# secs_q84_v2.net
KiCad netlist of a schematic drawn in EAGLE
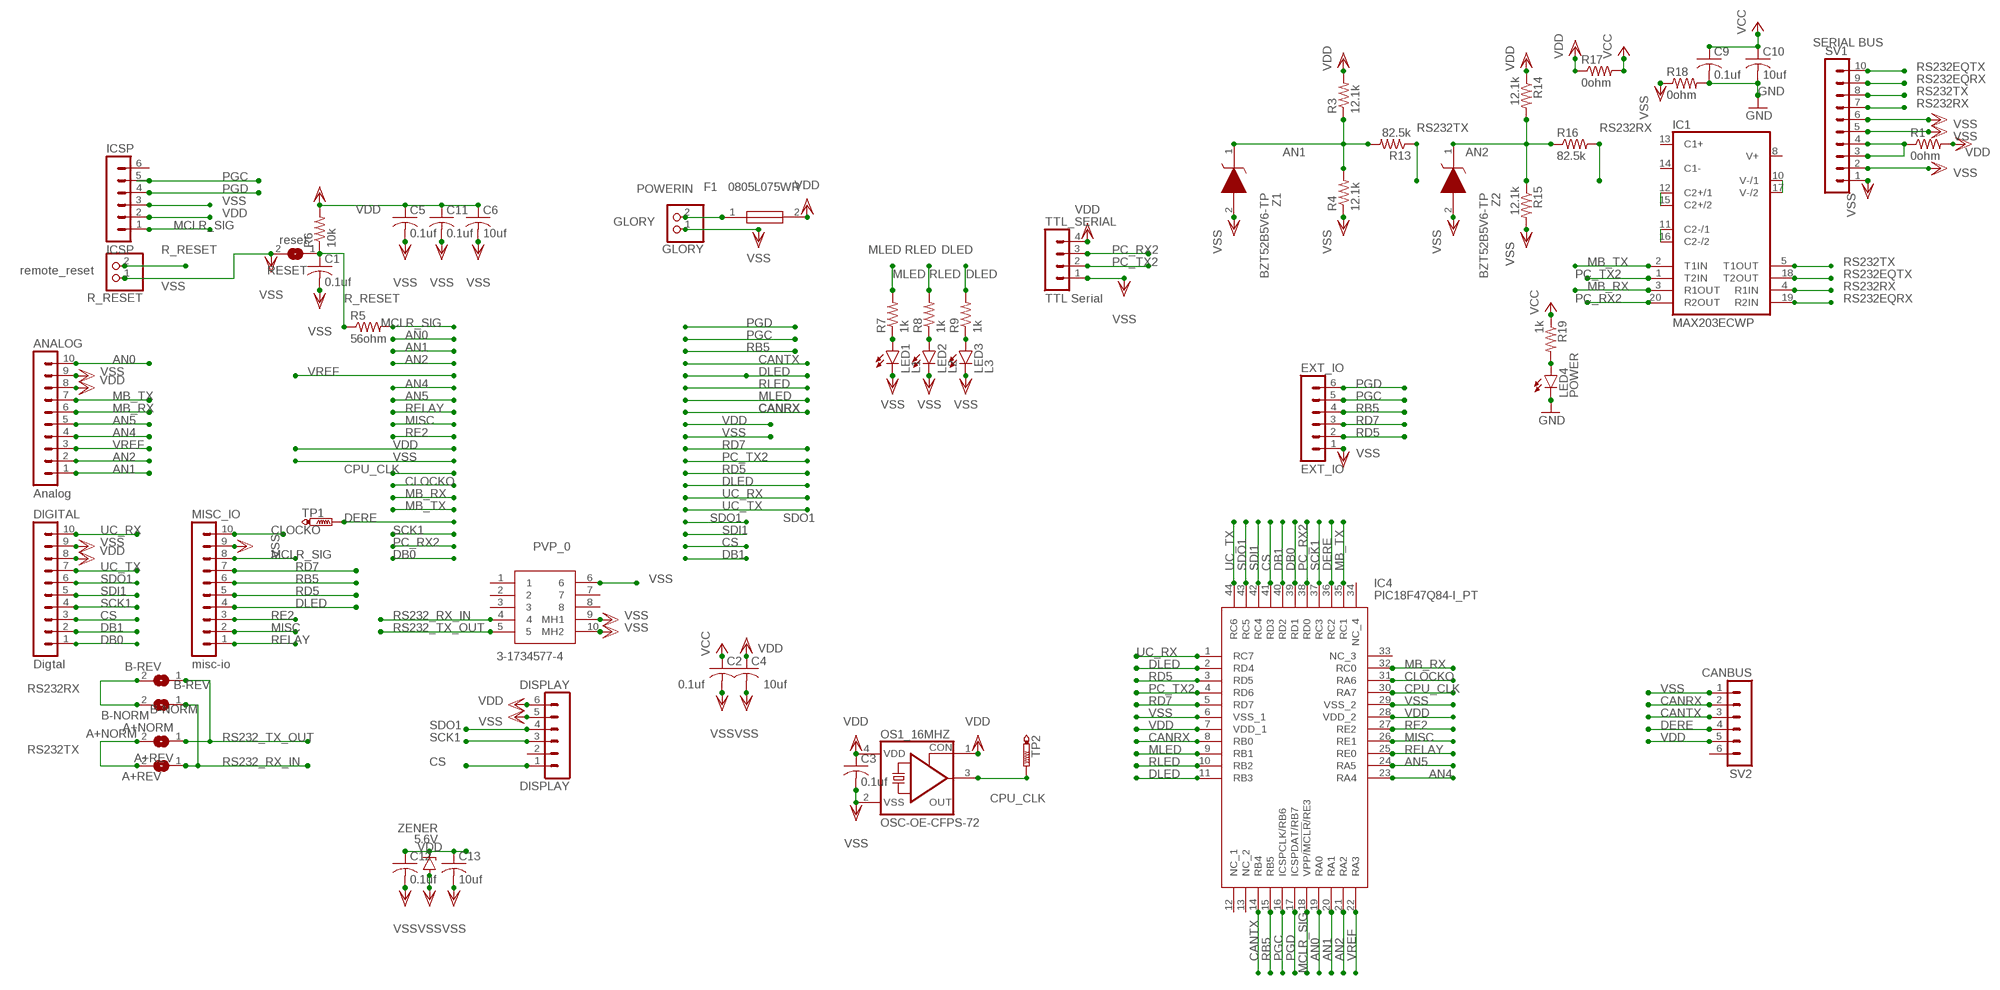
[diagram p0: schematic, sheet 1]

(export (version "E")
  (design (tool "Eeschema 10.0.6"))
  (components
    (comp (ref "A+NORM")
      (value "A+NORM")
      (footprint "eagle-import:SJ")
      (libsource (lib "eagle-import") (part "SJ"))
    )
    (comp (ref "A+REV")
      (value "A+REV")
      (footprint "eagle-import:SJ")
      (libsource (lib "eagle-import") (part "SJ"))
    )
    (comp (ref "ANALOG")
      (value "Analog")
      (footprint "eagle-import:MA10-1")
      (libsource (lib "eagle-import") (part "MA10-1"))
    )
    (comp (ref "B-NORM")
      (value "B-NORM")
      (footprint "eagle-import:SJ")
      (libsource (lib "eagle-import") (part "SJ"))
    )
    (comp (ref "B-REV")
      (value "B-REV")
      (footprint "eagle-import:SJ")
      (libsource (lib "eagle-import") (part "SJ"))
    )
    (comp (ref "C1")
      (value "0.1uf")
      (footprint "eagle-import:C0805")
      (libsource (lib "eagle-import") (part "C-USC0805"))
    )
    (comp (ref "C2")
      (value "0.1uf")
      (footprint "eagle-import:C0805")
      (libsource (lib "eagle-import") (part "C-USC0805"))
    )
    (comp (ref "C3")
      (value "0.1uf")
      (footprint "eagle-import:C0805")
      (libsource (lib "eagle-import") (part "C-USC0805"))
    )
    (comp (ref "C4")
      (value "10uf")
      (footprint "eagle-import:C0805")
      (libsource (lib "eagle-import") (part "C-USC0805"))
    )
    (comp (ref "C5")
      (value "0.1uf")
      (footprint "eagle-import:C0805")
      (libsource (lib "eagle-import") (part "C-USC0805"))
    )
    (comp (ref "C6")
      (value "10uf")
      (footprint "eagle-import:C0805")
      (libsource (lib "eagle-import") (part "C-USC0805"))
    )
    (comp (ref "C9")
      (value "0.1uf")
      (footprint "eagle-import:C0805")
      (libsource (lib "eagle-import") (part "C-USC0805"))
    )
    (comp (ref "C10")
      (value "10uf")
      (footprint "eagle-import:C0805")
      (libsource (lib "eagle-import") (part "C-USC0805"))
    )
    (comp (ref "C11")
      (value "0.1uf")
      (footprint "eagle-import:C0805")
      (libsource (lib "eagle-import") (part "C-USC0805"))
    )
    (comp (ref "C12")
      (value "0.1uf")
      (footprint "eagle-import:C0805")
      (libsource (lib "eagle-import") (part "C-USC0805"))
    )
    (comp (ref "C13")
      (value "10uf")
      (footprint "eagle-import:C0805")
      (libsource (lib "eagle-import") (part "C-USC0805"))
    )
    (comp (ref "DIGITAL")
      (value "Digtal")
      (footprint "eagle-import:MA10-1")
      (libsource (lib "eagle-import") (part "MA10-1"))
    )
    (comp (ref "DISPLAY")
      (value "DISPLAY")
      (footprint "eagle-import:MA06-1")
      (libsource (lib "eagle-import") (part "MA06-1"))
    )
    (comp (ref "EXT_IO")
      (value "EXT_IO")
      (footprint "eagle-import:MA06-1")
      (libsource (lib "eagle-import") (part "MA06-1"))
    )
    (comp (ref "F1")
      (value "0805L075WR")
      (footprint "eagle-import:FUSC2114X125N")
      (fields (field (name "MOUSER_PART_NUMBER") "576-0805L075WR"))
      (libsource (lib "eagle-import") (part "0805L075WR"))
    )
    (comp (ref "GLORY")
      (value "GLORY")
      (footprint "eagle-import:1X02")
      (libsource (lib "eagle-import") (part "PINHD-1X2"))
    )
    (comp (ref "IC1")
      (value "MAX203ECWP")
      (footprint "eagle-import:SO20L")
      (fields (field (name "MPN") "MAX203ECWP+G36"))
      (libsource (lib "eagle-import") (part "MAX203ECWP"))
    )
    (comp (ref "IC4")
      (value "PIC18F47Q84-I_PT")
      (footprint "eagle-import:QFP80P1200X1200X120-44N")
      (fields
        (field (name "MANUFACTURER_PART_NUMBER") "PIC18F47Q84-I/PT")
        (field (name "MOUSER_PART_NUMBER") "579-PIC18F47Q84-I/PT")
      )
      (libsource (lib "eagle-import") (part "PIC18F47Q84-I_PT"))
    )
    (comp (ref "ICSP")
      (value "ICSP")
      (footprint "eagle-import:MA06-1")
      (libsource (lib "eagle-import") (part "MA06-1"))
    )
    (comp (ref "LED1")
      (value "L1")
      (footprint "eagle-import:CHIPLED_0805")
      (libsource (lib "eagle-import") (part "LEDCHIPLED_0805"))
    )
    (comp (ref "LED2")
      (value "L2")
      (footprint "eagle-import:CHIPLED_0805")
      (libsource (lib "eagle-import") (part "LEDCHIPLED_0805"))
    )
    (comp (ref "LED3")
      (value "L3")
      (footprint "eagle-import:CHIPLED_0805")
      (libsource (lib "eagle-import") (part "LEDCHIPLED_0805"))
    )
    (comp (ref "LED4")
      (value "POWER")
      (footprint "eagle-import:CHIP-LED0603")
      (libsource (lib "eagle-import") (part "LEDCHIP-LED0603"))
    )
    (comp (ref "MISC_IO")
      (value "misc-io")
      (footprint "eagle-import:MA10-1")
      (libsource (lib "eagle-import") (part "MA10-1"))
    )
    (comp (ref "OS1_16MHZ")
      (value "OSC-OE-CFPS-72")
      (footprint "eagle-import:7.2X5.2-4-PAD")
      (libsource (lib "eagle-import") (part "OSC-OE-CFPS-72"))
    )
    (comp (ref "PVP_0")
      (value "3-1734577-4")
      (footprint "eagle-import:317345774")
      (fields (field (name "MOUSER_PART_NUMBER") "571-3-1734577-4"))
      (libsource (lib "eagle-import") (part "3-1734577-4"))
    )
    (comp (ref "R1")
      (value "0ohm")
      (footprint "eagle-import:R0805")
      (libsource (lib "eagle-import") (part "R-US_R0805"))
    )
    (comp (ref "R3")
      (value "12.1k")
      (footprint "eagle-import:R0805")
      (libsource (lib "eagle-import") (part "R-US_R0805"))
    )
    (comp (ref "R4")
      (value "12.1k")
      (footprint "eagle-import:R0805")
      (libsource (lib "eagle-import") (part "R-US_R0805"))
    )
    (comp (ref "R5")
      (value "56ohm")
      (footprint "eagle-import:R0805")
      (libsource (lib "eagle-import") (part "R-US_R0805"))
    )
    (comp (ref "R6")
      (value "10k")
      (footprint "eagle-import:R0805")
      (libsource (lib "eagle-import") (part "R-US_R0805"))
    )
    (comp (ref "R7")
      (value "1k")
      (footprint "eagle-import:R0805")
      (libsource (lib "eagle-import") (part "R-US_R0805"))
    )
    (comp (ref "R8")
      (value "1k")
      (footprint "eagle-import:R0805")
      (libsource (lib "eagle-import") (part "R-US_R0805"))
    )
    (comp (ref "R9")
      (value "1k")
      (footprint "eagle-import:R0805")
      (libsource (lib "eagle-import") (part "R-US_R0805"))
    )
    (comp (ref "R13")
      (value "82.5k")
      (footprint "eagle-import:R0805")
      (libsource (lib "eagle-import") (part "R-US_R0805"))
    )
    (comp (ref "R14")
      (value "12.1k")
      (footprint "eagle-import:R0805")
      (libsource (lib "eagle-import") (part "R-US_R0805"))
    )
    (comp (ref "R15")
      (value "12.1k")
      (footprint "eagle-import:R0805")
      (libsource (lib "eagle-import") (part "R-US_R0805"))
    )
    (comp (ref "R16")
      (value "82.5k")
      (footprint "eagle-import:R0805")
      (libsource (lib "eagle-import") (part "R-US_R0805"))
    )
    (comp (ref "R17")
      (value "0ohm")
      (footprint "eagle-import:R0805")
      (libsource (lib "eagle-import") (part "R-US_R0805"))
    )
    (comp (ref "R18")
      (value "0ohm")
      (footprint "eagle-import:R0805")
      (libsource (lib "eagle-import") (part "R-US_R0805"))
    )
    (comp (ref "R19")
      (value "1k")
      (footprint "eagle-import:R0805")
      (libsource (lib "eagle-import") (part "R-US_R0805"))
    )
    (comp (ref "RESET")
      (value "reset")
      (footprint "eagle-import:SJ")
      (libsource (lib "eagle-import") (part "SJ"))
    )
    (comp (ref "R_RESET")
      (value "remote_reset")
      (footprint "eagle-import:1X02")
      (libsource (lib "eagle-import") (part "PINHD-1X2"))
    )
    (comp (ref "SV1")
      (value "SERIAL BUS")
      (footprint "eagle-import:MA10-1")
      (libsource (lib "eagle-import") (part "MA10-1"))
    )
    (comp (ref "SV2")
      (value "CANBUS")
      (footprint "eagle-import:MA06-1")
      (libsource (lib "eagle-import") (part "MA06-1"))
    )
    (comp (ref "TP1")
      (value "PTR1PAD1-13")
      (footprint "eagle-import:P1-13")
      (libsource (lib "eagle-import") (part "PTR1PAD1-13"))
    )
    (comp (ref "TP2")
      (value "PTR1PAD1-13")
      (footprint "eagle-import:P1-13")
      (libsource (lib "eagle-import") (part "PTR1PAD1-13"))
    )
    (comp (ref "TTL_SERIAL")
      (value "TTL Serial")
      (footprint "eagle-import:MA04-1")
      (libsource (lib "eagle-import") (part "MA04-1"))
    )
    (comp (ref "Z1")
      (value "BZT52B5V6-TP")
      (footprint "eagle-import:SOD3716X135N")
      (fields (field (name "MOUSER_PART_NUMBER") "833-BZT52B5V6-TP"))
      (libsource (lib "eagle-import") (part "BZT52B5V6-TP"))
    )
    (comp (ref "Z2")
      (value "BZT52B5V6-TP")
      (footprint "eagle-import:SOD3716X135N")
      (fields (field (name "MOUSER_PART_NUMBER") "833-BZT52B5V6-TP"))
      (libsource (lib "eagle-import") (part "BZT52B5V6-TP"))
    )
    (comp (ref "ZENER")
      (value "5.6V")
      (footprint "eagle-import:SMB")
      (libsource (lib "eagle-import") (part "ZENER-DIODESMB"))
    )
  )
  (nets
    (net (code "1") (name "/AN0") (class "Default")
      (node (ref "ANALOG") (pin "10") (pinfunction "10_10") (pintype "passive"))
      (node (ref "IC4") (pin "19") (pinfunction "RA0_19") (pintype "bidirectional"))
    )
    (net (code "2") (name "/AN1") (class "Default")
      (node (ref "ANALOG") (pin "1") (pinfunction "1_1") (pintype "passive"))
      (node (ref "IC4") (pin "20") (pinfunction "RA1_20") (pintype "bidirectional"))
      (node (ref "R13") (pin "2") (pinfunction "2_2") (pintype "passive"))
      (node (ref "R3") (pin "1") (pinfunction "1_1") (pintype "passive"))
      (node (ref "R4") (pin "2") (pinfunction "2_2") (pintype "passive"))
      (node (ref "Z1") (pin "1") (pinfunction "K_1") (pintype "bidirectional"))
    )
    (net (code "3") (name "/AN2") (class "Default")
      (node (ref "ANALOG") (pin "2") (pinfunction "2_2") (pintype "passive"))
      (node (ref "IC4") (pin "21") (pinfunction "RA2_21") (pintype "bidirectional"))
      (node (ref "R14") (pin "2") (pinfunction "2_2") (pintype "passive"))
      (node (ref "R15") (pin "1") (pinfunction "1_1") (pintype "passive"))
      (node (ref "R16") (pin "1") (pinfunction "1_1") (pintype "passive"))
      (node (ref "Z2") (pin "1") (pinfunction "K_1") (pintype "bidirectional"))
    )
    (net (code "4") (name "/AN4") (class "Default")
      (node (ref "ANALOG") (pin "4") (pinfunction "4_4") (pintype "passive"))
      (node (ref "IC4") (pin "23") (pinfunction "RA4_23") (pintype "bidirectional"))
    )
    (net (code "5") (name "/AN5") (class "Default")
      (node (ref "ANALOG") (pin "5") (pinfunction "5_5") (pintype "passive"))
      (node (ref "IC4") (pin "24") (pinfunction "RA5_24") (pintype "bidirectional"))
    )
    (net (code "6") (name "/CANRX") (class "Default")
      (node (ref "IC4") (pin "8") (pinfunction "RB0_8") (pintype "bidirectional"))
      (node (ref "SV2") (pin "2") (pinfunction "2_2") (pintype "passive"))
    )
    (net (code "7") (name "/CANTX") (class "Default")
      (node (ref "IC4") (pin "14") (pinfunction "RB4_14") (pintype "bidirectional"))
      (node (ref "SV2") (pin "3") (pinfunction "3_3") (pintype "passive"))
    )
    (net (code "8") (name "/CLOCKO") (class "Default")
      (node (ref "IC4") (pin "31") (pinfunction "RA6_31") (pintype "bidirectional"))
      (node (ref "MISC_IO") (pin "10") (pinfunction "10_10") (pintype "passive"))
    )
    (net (code "9") (name "/CPU_CLK") (class "Default")
      (node (ref "IC4") (pin "30") (pinfunction "RA7_30") (pintype "bidirectional"))
      (node (ref "OS1_16MHZ") (pin "3") (pinfunction "OUT_3") (pintype "output"))
      (node (ref "TP2") (pin "TP") (pinfunction "TP_TP") (pintype "input"))
    )
    (net (code "10") (name "/CS") (class "Default")
      (node (ref "DIGITAL") (pin "3") (pinfunction "3_3") (pintype "passive"))
      (node (ref "DISPLAY") (pin "1") (pinfunction "1_1") (pintype "passive"))
      (node (ref "IC4") (pin "41") (pinfunction "RD3_41") (pintype "bidirectional"))
    )
    (net (code "11") (name "/DB0") (class "Default")
      (node (ref "DIGITAL") (pin "1") (pinfunction "1_1") (pintype "passive"))
      (node (ref "IC4") (pin "39") (pinfunction "RD1_39") (pintype "bidirectional"))
    )
    (net (code "12") (name "/DB1") (class "Default")
      (node (ref "DIGITAL") (pin "2") (pinfunction "2_2") (pintype "passive"))
      (node (ref "IC4") (pin "40") (pinfunction "RD2_40") (pintype "bidirectional"))
    )
    (net (code "13") (name "/DERE") (class "Default")
      (node (ref "IC4") (pin "36") (pinfunction "RC2_36") (pintype "bidirectional"))
      (node (ref "SV2") (pin "4") (pinfunction "4_4") (pintype "passive"))
      (node (ref "TP1") (pin "TP") (pinfunction "TP_TP") (pintype "input"))
    )
    (net (code "14") (name "/DLED") (class "Default")
      (node (ref "IC4") (pin "11") (pinfunction "RB3_11") (pintype "bidirectional"))
      (node (ref "IC4") (pin "2") (pinfunction "RD4_2") (pintype "bidirectional"))
      (node (ref "MISC_IO") (pin "4") (pinfunction "4_4") (pintype "passive"))
      (node (ref "R9") (pin "2") (pinfunction "2_2") (pintype "passive"))
    )
    (net (code "15") (name "/MB_RX") (class "Default")
      (node (ref "ANALOG") (pin "6") (pinfunction "6_6") (pintype "passive"))
      (node (ref "IC1") (pin "3") (pinfunction "R1OUT_3") (pintype "output"))
      (node (ref "IC4") (pin "32") (pinfunction "RC0_32") (pintype "bidirectional"))
    )
    (net (code "16") (name "/MB_TX") (class "Default")
      (node (ref "ANALOG") (pin "7") (pinfunction "7_7") (pintype "passive"))
      (node (ref "IC1") (pin "2") (pinfunction "T1IN_2") (pintype "input"))
      (node (ref "IC4") (pin "35") (pinfunction "RC1_35") (pintype "bidirectional"))
    )
    (net (code "17") (name "/MCLR_SIG") (class "Default")
      (node (ref "IC4") (pin "18") (pinfunction "VPP/~{MCLR}/RE3_18") (pintype "bidirectional"))
      (node (ref "ICSP") (pin "1") (pinfunction "1_1") (pintype "passive"))
      (node (ref "MISC_IO") (pin "8") (pinfunction "8_8") (pintype "passive"))
      (node (ref "R5") (pin "2") (pinfunction "2_2") (pintype "passive"))
    )
    (net (code "18") (name "/MISC") (class "Default")
      (node (ref "IC4") (pin "26") (pinfunction "RE1_26") (pintype "bidirectional"))
      (node (ref "MISC_IO") (pin "2") (pinfunction "2_2") (pintype "passive"))
    )
    (net (code "19") (name "/MLED") (class "Default")
      (node (ref "IC4") (pin "9") (pinfunction "RB1_9") (pintype "bidirectional"))
      (node (ref "R7") (pin "2") (pinfunction "2_2") (pintype "passive"))
    )
    (net (code "20") (name "/PC_RX2") (class "Default")
      (node (ref "IC1") (pin "20") (pinfunction "R2OUT_20") (pintype "output"))
      (node (ref "IC4") (pin "38") (pinfunction "RD0_38") (pintype "bidirectional"))
      (node (ref "TTL_SERIAL") (pin "3") (pinfunction "3_3") (pintype "passive"))
    )
    (net (code "21") (name "/PC_TX2") (class "Default")
      (node (ref "IC1") (pin "1") (pinfunction "T2IN_1") (pintype "input"))
      (node (ref "IC4") (pin "4") (pinfunction "RD6_4") (pintype "bidirectional"))
      (node (ref "TTL_SERIAL") (pin "2") (pinfunction "2_2") (pintype "passive"))
    )
    (net (code "22") (name "/PGC") (class "Default")
      (node (ref "EXT_IO") (pin "5") (pinfunction "5_5") (pintype "passive"))
      (node (ref "IC4") (pin "16") (pinfunction "ICSPCLK/RB6_16") (pintype "bidirectional"))
      (node (ref "ICSP") (pin "5") (pinfunction "5_5") (pintype "passive"))
    )
    (net (code "23") (name "/PGD") (class "Default")
      (node (ref "EXT_IO") (pin "6") (pinfunction "6_6") (pintype "passive"))
      (node (ref "IC4") (pin "17") (pinfunction "ICSPDAT/RB7_17") (pintype "bidirectional"))
      (node (ref "ICSP") (pin "4") (pinfunction "4_4") (pintype "passive"))
    )
    (net (code "24") (name "/POWERIN") (class "Default")
      (node (ref "F1") (pin "1") (pinfunction "1_1") (pintype "bidirectional"))
      (node (ref "GLORY") (pin "2") (pinfunction "2_2") (pintype "passive"))
    )
    (net (code "25") (name "/RB5") (class "Default")
      (node (ref "EXT_IO") (pin "4") (pinfunction "4_4") (pintype "passive"))
      (node (ref "IC4") (pin "15") (pinfunction "RB5_15") (pintype "bidirectional"))
      (node (ref "MISC_IO") (pin "6") (pinfunction "6_6") (pintype "passive"))
    )
    (net (code "26") (name "/RD5") (class "Default")
      (node (ref "EXT_IO") (pin "2") (pinfunction "2_2") (pintype "passive"))
      (node (ref "IC4") (pin "3") (pinfunction "RD5_3") (pintype "bidirectional"))
      (node (ref "MISC_IO") (pin "5") (pinfunction "5_5") (pintype "passive"))
    )
    (net (code "27") (name "/RD7") (class "Default")
      (node (ref "EXT_IO") (pin "3") (pinfunction "3_3") (pintype "passive"))
      (node (ref "IC4") (pin "5") (pinfunction "RD7_5") (pintype "bidirectional"))
      (node (ref "MISC_IO") (pin "7") (pinfunction "7_7") (pintype "passive"))
    )
    (net (code "28") (name "/RE2") (class "Default")
      (node (ref "IC4") (pin "27") (pinfunction "RE2_27") (pintype "bidirectional"))
      (node (ref "MISC_IO") (pin "3") (pinfunction "3_3") (pintype "passive"))
    )
    (net (code "29") (name "/RELAY") (class "Default")
      (node (ref "IC4") (pin "25") (pinfunction "RE0_25") (pintype "bidirectional"))
      (node (ref "MISC_IO") (pin "1") (pinfunction "1_1") (pintype "passive"))
    )
    (net (code "30") (name "/RLED") (class "Default")
      (node (ref "IC4") (pin "10") (pinfunction "RB2_10") (pintype "bidirectional"))
      (node (ref "R8") (pin "2") (pinfunction "2_2") (pintype "passive"))
    )
    (net (code "31") (name "/RS232EQRX") (class "Default")
      (node (ref "IC1") (pin "19") (pinfunction "R2IN_19") (pintype "input"))
      (node (ref "SV1") (pin "9") (pinfunction "9_9") (pintype "passive"))
    )
    (net (code "32") (name "/RS232EQTX") (class "Default")
      (node (ref "IC1") (pin "18") (pinfunction "T2OUT_18") (pintype "output"))
      (node (ref "SV1") (pin "10") (pinfunction "10_10") (pintype "passive"))
    )
    (net (code "33") (name "/RS232RX") (class "Default")
      (node (ref "B-NORM") (pin "2") (pinfunction "2_2") (pintype "passive"))
      (node (ref "B-REV") (pin "2") (pinfunction "2_2") (pintype "passive"))
      (node (ref "IC1") (pin "4") (pinfunction "R1IN_4") (pintype "input"))
      (node (ref "R16") (pin "2") (pinfunction "2_2") (pintype "passive"))
      (node (ref "SV1") (pin "7") (pinfunction "7_7") (pintype "passive"))
    )
    (net (code "34") (name "/RS232TX") (class "Default")
      (node (ref "A+NORM") (pin "2") (pinfunction "2_2") (pintype "passive"))
      (node (ref "A+REV") (pin "2") (pinfunction "2_2") (pintype "passive"))
      (node (ref "IC1") (pin "5") (pinfunction "T1OUT_5") (pintype "output"))
      (node (ref "R13") (pin "1") (pinfunction "1_1") (pintype "passive"))
      (node (ref "SV1") (pin "8") (pinfunction "8_8") (pintype "passive"))
    )
    (net (code "35") (name "/RS232_RX_IN") (class "Default")
      (node (ref "A+REV") (pin "1") (pinfunction "1_1") (pintype "passive"))
      (node (ref "B-NORM") (pin "1") (pinfunction "1_1") (pintype "passive"))
      (node (ref "PVP_0") (pin "4") (pinfunction "4_4") (pintype "bidirectional"))
    )
    (net (code "36") (name "/RS232_TX_OUT") (class "Default")
      (node (ref "A+NORM") (pin "1") (pinfunction "1_1") (pintype "passive"))
      (node (ref "B-REV") (pin "1") (pinfunction "1_1") (pintype "passive"))
      (node (ref "PVP_0") (pin "5") (pinfunction "5_5") (pintype "bidirectional"))
    )
    (net (code "37") (name "/R_RESET") (class "Default")
      (node (ref "C1") (pin "1") (pinfunction "1_1") (pintype "passive"))
      (node (ref "R5") (pin "1") (pinfunction "1_1") (pintype "passive"))
      (node (ref "R6") (pin "1") (pinfunction "1_1") (pintype "passive"))
      (node (ref "RESET") (pin "1") (pinfunction "1_1") (pintype "passive"))
      (node (ref "R_RESET") (pin "2") (pinfunction "2_2") (pintype "passive"))
    )
    (net (code "38") (name "/SCK1") (class "Default")
      (node (ref "DIGITAL") (pin "4") (pinfunction "4_4") (pintype "passive"))
      (node (ref "DISPLAY") (pin "3") (pinfunction "3_3") (pintype "passive"))
      (node (ref "IC4") (pin "37") (pinfunction "RC3_37") (pintype "bidirectional"))
    )
    (net (code "39") (name "/SDI1") (class "Default")
      (node (ref "DIGITAL") (pin "5") (pinfunction "5_5") (pintype "passive"))
      (node (ref "IC4") (pin "42") (pinfunction "RC4_42") (pintype "bidirectional"))
    )
    (net (code "40") (name "/SDO1") (class "Default")
      (node (ref "DIGITAL") (pin "6") (pinfunction "6_6") (pintype "passive"))
      (node (ref "DISPLAY") (pin "4") (pinfunction "4_4") (pintype "passive"))
      (node (ref "IC4") (pin "43") (pinfunction "RC5_43") (pintype "bidirectional"))
    )
    (net (code "41") (name "/UC_RX") (class "Default")
      (node (ref "DIGITAL") (pin "10") (pinfunction "10_10") (pintype "passive"))
      (node (ref "IC4") (pin "1") (pinfunction "RC7_1") (pintype "bidirectional"))
    )
    (net (code "42") (name "/UC_TX") (class "Default")
      (node (ref "DIGITAL") (pin "7") (pinfunction "7_7") (pintype "passive"))
      (node (ref "IC4") (pin "44") (pinfunction "RC6_44") (pintype "bidirectional"))
    )
    (net (code "43") (name "/VREF") (class "Default")
      (node (ref "ANALOG") (pin "3") (pinfunction "3_3") (pintype "passive"))
      (node (ref "IC4") (pin "22") (pinfunction "RA3_22") (pintype "bidirectional"))
    )
    (net (code "44") (name "GND") (class "Default")
      (node (ref "C10") (pin "2") (pinfunction "2_2") (pintype "passive"))
      (node (ref "C9") (pin "2") (pinfunction "2_2") (pintype "passive"))
      (node (ref "LED4") (pin "C") (pinfunction "C_C") (pintype "passive"))
      (node (ref "R18") (pin "2") (pinfunction "2_2") (pintype "passive"))
    )
    (net (code "45") (name "Net-(IC1A-C2+{slash}1)") (class "Default")
      (node (ref "IC1") (pin "12") (pinfunction "C2+/1_12") (pintype "passive"))
      (node (ref "IC1") (pin "15") (pinfunction "C2+/2_15") (pintype "passive"))
    )
    (net (code "46") (name "Net-(IC1A-C2-{slash}1)") (class "Default")
      (node (ref "IC1") (pin "11") (pinfunction "C2-/1_11") (pintype "passive"))
      (node (ref "IC1") (pin "16") (pinfunction "C2-/2_16") (pintype "passive"))
    )
    (net (code "47") (name "Net-(IC1A-V-{slash}1)") (class "Default")
      (node (ref "IC1") (pin "10") (pinfunction "V-/1_10") (pintype "passive"))
      (node (ref "IC1") (pin "17") (pinfunction "V-/2_17") (pintype "passive"))
    )
    (net (code "48") (name "Net-(LED1-PadA)") (class "Default")
      (node (ref "LED1") (pin "A") (pinfunction "A_A") (pintype "passive"))
      (node (ref "R7") (pin "1") (pinfunction "1_1") (pintype "passive"))
    )
    (net (code "49") (name "Net-(LED2-PadA)") (class "Default")
      (node (ref "LED2") (pin "A") (pinfunction "A_A") (pintype "passive"))
      (node (ref "R8") (pin "1") (pinfunction "1_1") (pintype "passive"))
    )
    (net (code "50") (name "Net-(LED3-PadA)") (class "Default")
      (node (ref "LED3") (pin "A") (pinfunction "A_A") (pintype "passive"))
      (node (ref "R9") (pin "1") (pinfunction "1_1") (pintype "passive"))
    )
    (net (code "51") (name "Net-(LED4-PadA)") (class "Default")
      (node (ref "LED4") (pin "A") (pinfunction "A_A") (pintype "passive"))
      (node (ref "R19") (pin "2") (pinfunction "2_2") (pintype "passive"))
    )
    (net (code "52") (name "Net-(R1-Pad1)") (class "Default")
      (node (ref "R1") (pin "1") (pinfunction "1_1") (pintype "passive"))
      (node (ref "SV1") (pin "3") (pinfunction "3_3") (pintype "passive"))
      (node (ref "SV1") (pin "4") (pinfunction "4_4") (pintype "passive"))
    )
    (net (code "53") (name "VCC") (class "Default")
      (node (ref "C10") (pin "1") (pinfunction "1_1") (pintype "passive"))
      (node (ref "C2") (pin "1") (pinfunction "1_1") (pintype "passive"))
      (node (ref "C9") (pin "1") (pinfunction "1_1") (pintype "passive"))
      (node (ref "R17") (pin "2") (pinfunction "2_2") (pintype "passive"))
      (node (ref "R19") (pin "1") (pinfunction "1_1") (pintype "passive"))
    )
    (net (code "54") (name "VDD") (class "Default")
      (node (ref "ANALOG") (pin "8") (pinfunction "8_8") (pintype "passive"))
      (node (ref "C11") (pin "1") (pinfunction "1_1") (pintype "passive"))
      (node (ref "C12") (pin "1") (pinfunction "1_1") (pintype "passive"))
      (node (ref "C13") (pin "1") (pinfunction "1_1") (pintype "passive"))
      (node (ref "C3") (pin "1") (pinfunction "1_1") (pintype "passive"))
      (node (ref "C4") (pin "1") (pinfunction "1_1") (pintype "passive"))
      (node (ref "C5") (pin "1") (pinfunction "1_1") (pintype "passive"))
      (node (ref "C6") (pin "1") (pinfunction "1_1") (pintype "passive"))
      (node (ref "DIGITAL") (pin "8") (pinfunction "8_8") (pintype "passive"))
      (node (ref "DISPLAY") (pin "6") (pinfunction "6_6") (pintype "passive"))
      (node (ref "F1") (pin "2") (pinfunction "2_2") (pintype "bidirectional"))
      (node (ref "IC4") (pin "28") (pinfunction "VDD_2_28") (pintype "bidirectional"))
      (node (ref "IC4") (pin "7") (pinfunction "VDD_1_7") (pintype "bidirectional"))
      (node (ref "ICSP") (pin "2") (pinfunction "2_2") (pintype "passive"))
      (node (ref "OS1_16MHZ") (pin "1") (pinfunction "CON_1") (pintype "input"))
      (node (ref "OS1_16MHZ") (pin "4") (pinfunction "VDD_4") (pintype "power_in"))
      (node (ref "R1") (pin "2") (pinfunction "2_2") (pintype "passive"))
      (node (ref "R14") (pin "1") (pinfunction "1_1") (pintype "passive"))
      (node (ref "R17") (pin "1") (pinfunction "1_1") (pintype "passive"))
      (node (ref "R3") (pin "2") (pinfunction "2_2") (pintype "passive"))
      (node (ref "R6") (pin "2") (pinfunction "2_2") (pintype "passive"))
      (node (ref "SV2") (pin "5") (pinfunction "5_5") (pintype "passive"))
      (node (ref "TTL_SERIAL") (pin "4") (pinfunction "4_4") (pintype "passive"))
      (node (ref "ZENER") (pin "C") (pinfunction "C_C") (pintype "passive"))
    )
    (net (code "55") (name "VSS") (class "Default")
      (node (ref "ANALOG") (pin "9") (pinfunction "9_9") (pintype "passive"))
      (node (ref "C1") (pin "2") (pinfunction "2_2") (pintype "passive"))
      (node (ref "C11") (pin "2") (pinfunction "2_2") (pintype "passive"))
      (node (ref "C12") (pin "2") (pinfunction "2_2") (pintype "passive"))
      (node (ref "C13") (pin "2") (pinfunction "2_2") (pintype "passive"))
      (node (ref "C2") (pin "2") (pinfunction "2_2") (pintype "passive"))
      (node (ref "C3") (pin "2") (pinfunction "2_2") (pintype "passive"))
      (node (ref "C4") (pin "2") (pinfunction "2_2") (pintype "passive"))
      (node (ref "C5") (pin "2") (pinfunction "2_2") (pintype "passive"))
      (node (ref "C6") (pin "2") (pinfunction "2_2") (pintype "passive"))
      (node (ref "DIGITAL") (pin "9") (pinfunction "9_9") (pintype "passive"))
      (node (ref "DISPLAY") (pin "5") (pinfunction "5_5") (pintype "passive"))
      (node (ref "EXT_IO") (pin "1") (pinfunction "1_1") (pintype "passive"))
      (node (ref "GLORY") (pin "1") (pinfunction "1_1") (pintype "passive"))
      (node (ref "IC4") (pin "29") (pinfunction "VSS_2_29") (pintype "bidirectional"))
      (node (ref "IC4") (pin "6") (pinfunction "VSS_1_6") (pintype "bidirectional"))
      (node (ref "ICSP") (pin "3") (pinfunction "3_3") (pintype "passive"))
      (node (ref "LED1") (pin "C") (pinfunction "C_C") (pintype "passive"))
      (node (ref "LED2") (pin "C") (pinfunction "C_C") (pintype "passive"))
      (node (ref "LED3") (pin "C") (pinfunction "C_C") (pintype "passive"))
      (node (ref "MISC_IO") (pin "9") (pinfunction "9_9") (pintype "passive"))
      (node (ref "OS1_16MHZ") (pin "2") (pinfunction "VSS_2") (pintype "power_in"))
      (node (ref "PVP_0") (pin "10") (pinfunction "MH2_10") (pintype "bidirectional"))
      (node (ref "PVP_0") (pin "6") (pinfunction "6_6") (pintype "bidirectional"))
      (node (ref "PVP_0") (pin "9") (pinfunction "MH1_9") (pintype "bidirectional"))
      (node (ref "R15") (pin "2") (pinfunction "2_2") (pintype "passive"))
      (node (ref "R18") (pin "1") (pinfunction "1_1") (pintype "passive"))
      (node (ref "R4") (pin "1") (pinfunction "1_1") (pintype "passive"))
      (node (ref "RESET") (pin "2") (pinfunction "2_2") (pintype "passive"))
      (node (ref "R_RESET") (pin "1") (pinfunction "1_1") (pintype "passive"))
      (node (ref "SV1") (pin "1") (pinfunction "1_1") (pintype "passive"))
      (node (ref "SV1") (pin "2") (pinfunction "2_2") (pintype "passive"))
      (node (ref "SV1") (pin "5") (pinfunction "5_5") (pintype "passive"))
      (node (ref "SV1") (pin "6") (pinfunction "6_6") (pintype "passive"))
      (node (ref "SV2") (pin "1") (pinfunction "1_1") (pintype "passive"))
      (node (ref "TTL_SERIAL") (pin "1") (pinfunction "1_1") (pintype "passive"))
      (node (ref "Z1") (pin "2") (pinfunction "A_2") (pintype "bidirectional"))
      (node (ref "Z2") (pin "2") (pinfunction "A_2") (pintype "bidirectional"))
      (node (ref "ZENER") (pin "A") (pinfunction "A_A") (pintype "passive"))
    )
    (net (code "56") (name "unconnected-(DISPLAY-Pad2)") (class "Default")
      (node (ref "DISPLAY") (pin "2") (pinfunction "2_2") (pintype "passive"))
    )
    (net (code "57") (name "unconnected-(IC1A-C1+-Pad13)") (class "Default")
      (node (ref "IC1") (pin "13") (pinfunction "C1+_13") (pintype "passive"))
    )
    (net (code "58") (name "unconnected-(IC1A-C1--Pad14)") (class "Default")
      (node (ref "IC1") (pin "14") (pinfunction "C1-_14") (pintype "passive"))
    )
    (net (code "59") (name "unconnected-(IC1A-V+-Pad8)") (class "Default")
      (node (ref "IC1") (pin "8") (pinfunction "V+_8") (pintype "passive"))
    )
    (net (code "60") (name "unconnected-(IC4-NC_1-Pad12)") (class "Default")
      (node (ref "IC4") (pin "12") (pinfunction "NC_1_12") (pintype "bidirectional"))
    )
    (net (code "61") (name "unconnected-(IC4-NC_2-Pad13)") (class "Default")
      (node (ref "IC4") (pin "13") (pinfunction "NC_2_13") (pintype "bidirectional"))
    )
    (net (code "62") (name "unconnected-(IC4-NC_3-Pad33)") (class "Default")
      (node (ref "IC4") (pin "33") (pinfunction "NC_3_33") (pintype "bidirectional"))
    )
    (net (code "63") (name "unconnected-(IC4-NC_4-Pad34)") (class "Default")
      (node (ref "IC4") (pin "34") (pinfunction "NC_4_34") (pintype "bidirectional"))
    )
    (net (code "64") (name "unconnected-(ICSP-Pad6)") (class "Default")
      (node (ref "ICSP") (pin "6") (pinfunction "6_6") (pintype "passive"))
    )
    (net (code "65") (name "unconnected-(PVP_0-Pad1)") (class "Default")
      (node (ref "PVP_0") (pin "1") (pinfunction "1_1") (pintype "bidirectional"))
    )
    (net (code "66") (name "unconnected-(PVP_0-Pad2)") (class "Default")
      (node (ref "PVP_0") (pin "2") (pinfunction "2_2") (pintype "bidirectional"))
    )
    (net (code "67") (name "unconnected-(PVP_0-Pad3)") (class "Default")
      (node (ref "PVP_0") (pin "3") (pinfunction "3_3") (pintype "bidirectional"))
    )
    (net (code "68") (name "unconnected-(PVP_0-Pad7)") (class "Default")
      (node (ref "PVP_0") (pin "7") (pinfunction "7_7") (pintype "bidirectional"))
    )
    (net (code "69") (name "unconnected-(PVP_0-Pad8)") (class "Default")
      (node (ref "PVP_0") (pin "8") (pinfunction "8_8") (pintype "bidirectional"))
    )
    (net (code "70") (name "unconnected-(SV2-Pad6)") (class "Default")
      (node (ref "SV2") (pin "6") (pinfunction "6_6") (pintype "passive"))
    )
  )
)
